# LED_Brightness_Adjuster.net
KiCad netlist of a schematic drawn in EAGLE
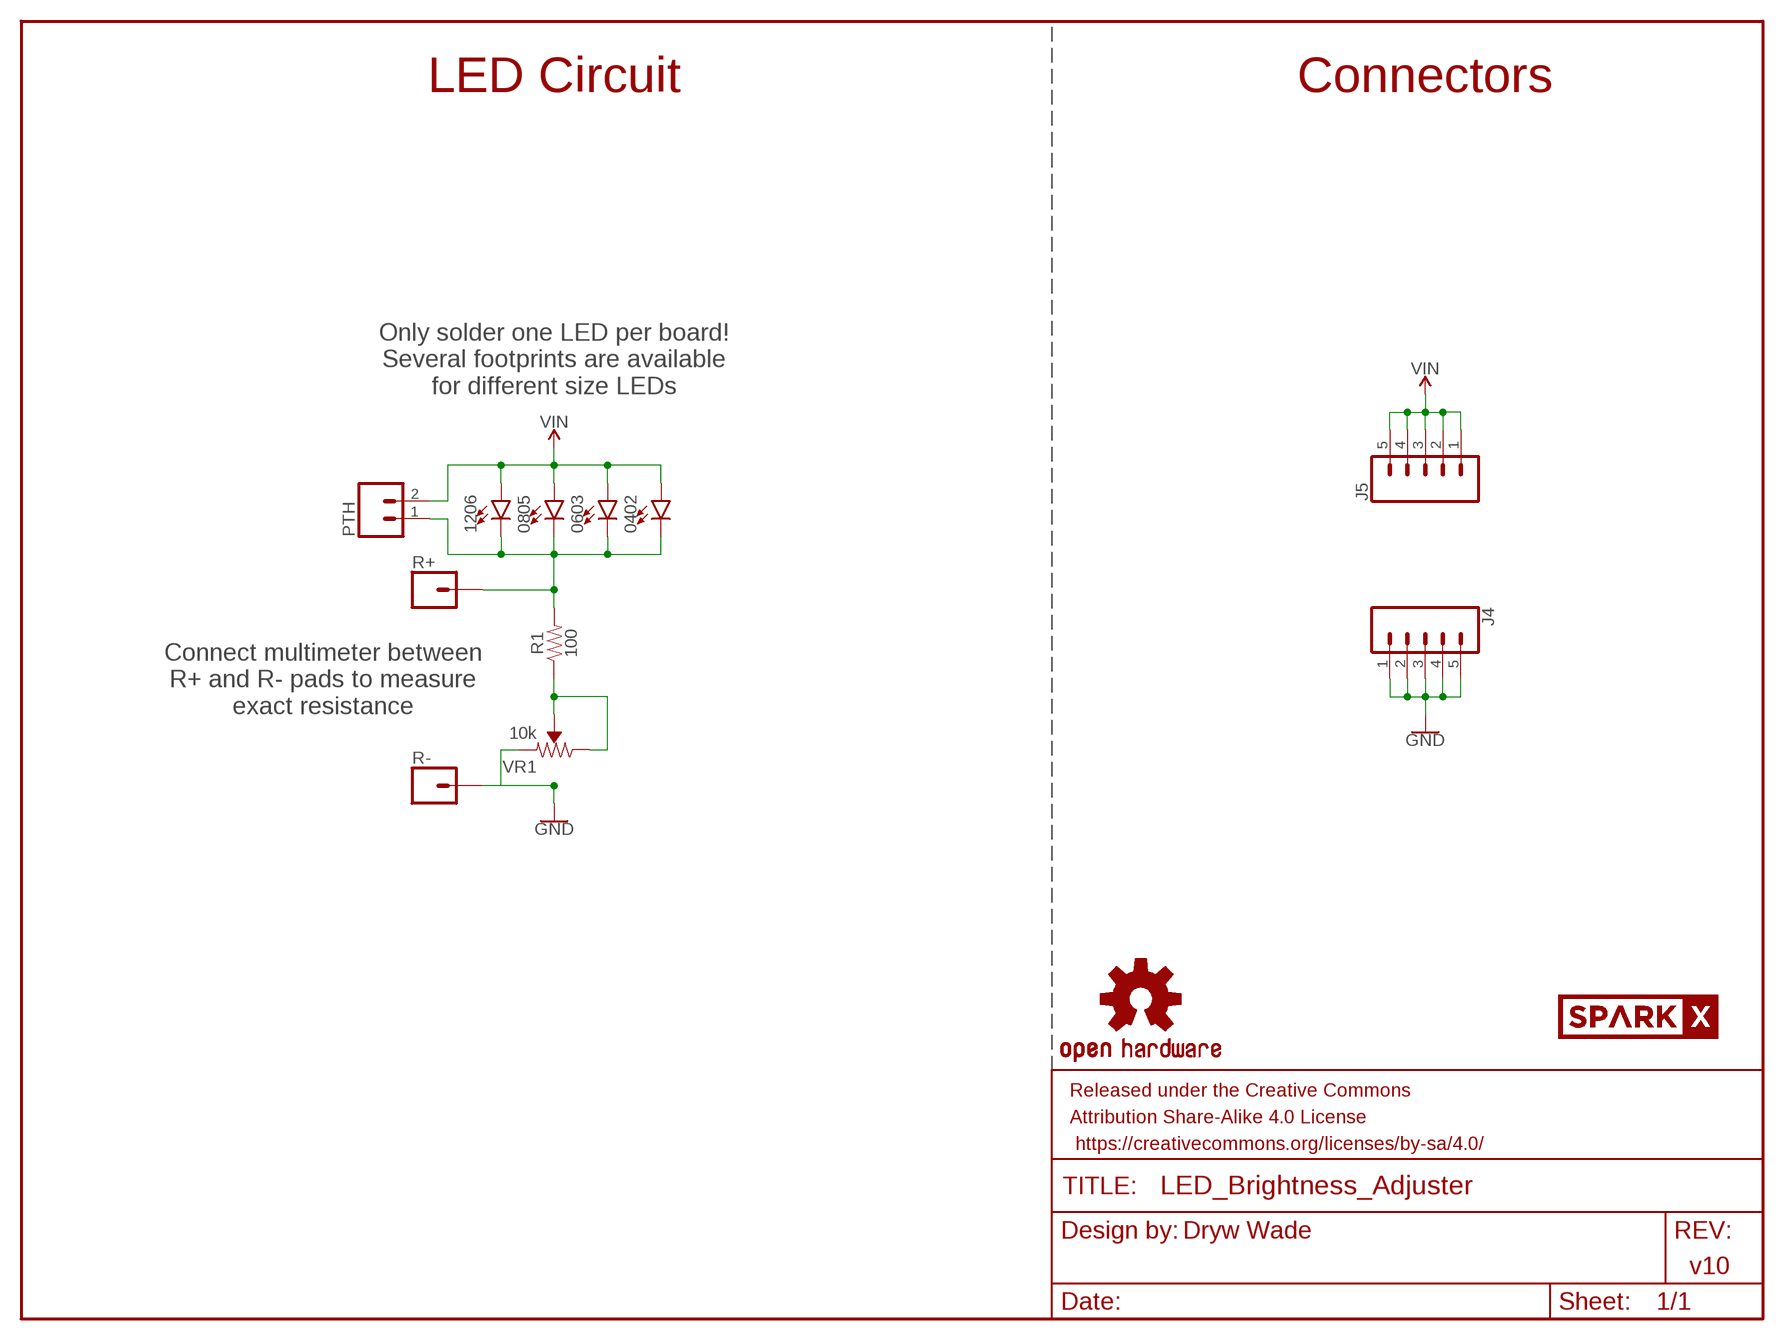
[diagram p0: schematic, sheet 1]

(export (version "E")
  (design (tool "Eeschema 10.0.6"))
  (components
    (comp (ref "0402")
      (value "RED")
      (footprint "eagle-import:LED-0402")
      (libsource (lib "eagle-import") (part "LED-RED_0402"))
    )
    (comp (ref "0603")
      (value "RED")
      (footprint "eagle-import:LED-0603")
      (libsource (lib "eagle-import") (part "LED-RED0603"))
    )
    (comp (ref "0805")
      (value "RED")
      (footprint "eagle-import:LED-0805")
      (libsource (lib "eagle-import") (part "LED-RED-0805"))
    )
    (comp (ref "1206")
      (value "RED")
      (footprint "eagle-import:LED-1206")
      (libsource (lib "eagle-import") (part "LED-RED1206"))
    )
    (comp (ref "FRAME1")
      (value "FRAME-LETTER")
      (footprint "eagle-import:CREATIVE_COMMONS")
      (libsource (lib "eagle-import") (part "FRAME-LETTER"))
    )
    (comp (ref "J4")
      (value "CONN_05")
      (footprint "eagle-import:1X05")
      (libsource (lib "eagle-import") (part "CONN_05"))
    )
    (comp (ref "J5")
      (value "CONN_05")
      (footprint "eagle-import:1X05")
      (libsource (lib "eagle-import") (part "CONN_05"))
    )
    (comp (ref "LOGO2")
      (value "OSHW-LOGOS")
      (footprint "eagle-import:OSHW-LOGO-S")
      (libsource (lib "eagle-import") (part "OSHW-LOGOS"))
    )
    (comp (ref "PTH")
      (value "CONN_02")
      (footprint "eagle-import:1X02")
      (libsource (lib "eagle-import") (part "CONN_02"))
    )
    (comp (ref "R+")
      (value "CONN_01")
      (footprint "eagle-import:1X01")
      (libsource (lib "eagle-import") (part "CONN_01"))
    )
    (comp (ref "R-")
      (value "CONN_01")
      (footprint "eagle-import:1X01")
      (libsource (lib "eagle-import") (part "CONN_01"))
    )
    (comp (ref "R1")
      (value "100")
      (footprint "eagle-import:AXIAL-0.3")
      (libsource (lib "eagle-import") (part "100OHM-HORIZ-1/4W-1%"))
    )
    (comp (ref "U$26")
      (value "SPARKX-LOGO5")
      (footprint "eagle-import:SPARKX-LARGE")
      (libsource (lib "eagle-import") (part "SPARKX-LOGO5"))
    )
    (comp (ref "U$27")
      (value "SPARKX-LOGO5")
      (footprint "eagle-import:SPARKX-LARGE")
      (libsource (lib "eagle-import") (part "SPARKX-LOGO5"))
    )
    (comp (ref "VR1")
      (value "10k")
      (footprint "eagle-import:TRIMPOT-PTH-3386U")
      (libsource (lib "eagle-import") (part "TRIMPOT-PTH-10MM-KNOB-1/2W-10%"))
    )
  )
  (nets
    (net (code "1") (name "GND") (class "Default")
      (node (ref "J4") (pin "1") (pinfunction "1_1") (pintype "passive"))
      (node (ref "J4") (pin "2") (pinfunction "2_2") (pintype "passive"))
      (node (ref "J4") (pin "3") (pinfunction "3_3") (pintype "passive"))
      (node (ref "J4") (pin "4") (pinfunction "4_4") (pintype "passive"))
      (node (ref "J4") (pin "5") (pinfunction "5_5") (pintype "passive"))
      (node (ref "R-") (pin "1") (pinfunction "1_1") (pintype "passive"))
      (node (ref "VR1") (pin "1") (pinfunction "CCW_1") (pintype "passive"))
    )
    (net (code "2") (name "Net-(R1-1)") (class "Default")
      (node (ref "R1") (pin "P$1") (pinfunction "1_P$1") (pintype "passive"))
      (node (ref "VR1") (pin "2") (pinfunction "WIPER_2") (pintype "passive"))
      (node (ref "VR1") (pin "3") (pinfunction "CW_3") (pintype "passive"))
    )
    (net (code "3") (name "Net-(R1-2)") (class "Default")
      (node (ref "0402") (pin "C") (pinfunction "C_C") (pintype "passive"))
      (node (ref "0603") (pin "C") (pinfunction "C_C") (pintype "passive"))
      (node (ref "0805") (pin "C") (pinfunction "C_C") (pintype "passive"))
      (node (ref "1206") (pin "C") (pinfunction "C_C") (pintype "passive"))
      (node (ref "PTH") (pin "1") (pinfunction "1_1") (pintype "passive"))
      (node (ref "R+") (pin "1") (pinfunction "1_1") (pintype "passive"))
      (node (ref "R1") (pin "P$2") (pinfunction "2_P$2") (pintype "passive"))
    )
    (net (code "4") (name "VIN") (class "Default")
      (node (ref "0402") (pin "A") (pinfunction "A_A") (pintype "passive"))
      (node (ref "0603") (pin "A") (pinfunction "A_A") (pintype "passive"))
      (node (ref "0805") (pin "A") (pinfunction "A_A") (pintype "passive"))
      (node (ref "1206") (pin "A") (pinfunction "A_A") (pintype "passive"))
      (node (ref "J5") (pin "1") (pinfunction "1_1") (pintype "passive"))
      (node (ref "J5") (pin "2") (pinfunction "2_2") (pintype "passive"))
      (node (ref "J5") (pin "3") (pinfunction "3_3") (pintype "passive"))
      (node (ref "J5") (pin "4") (pinfunction "4_4") (pintype "passive"))
      (node (ref "J5") (pin "5") (pinfunction "5_5") (pintype "passive"))
      (node (ref "PTH") (pin "2") (pinfunction "2_2") (pintype "passive"))
    )
  )
)
